# encoder.net
KiCad netlist of a schematic drawn in EAGLE
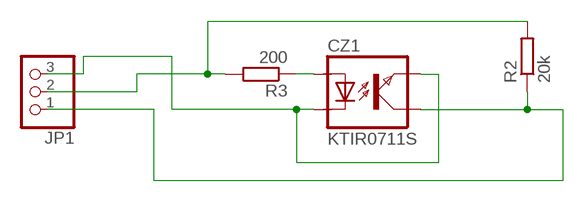
[diagram p0: schematic, sheet 1]

(export (version "E")
  (design (tool "Eeschema 10.0.6"))
  (components
    (comp (ref "CZ1")
      (value "KTIR0711S")
      (footprint "eagle-import:TOP")
      (libsource (lib "eagle-import") (part "KTIR0711S"))
    )
    (comp (ref "JP1")
      (value "PINHD-1X3")
      (footprint "eagle-import:1X03")
      (libsource (lib "eagle-import") (part "PINHD-1X3"))
    )
    (comp (ref "R2")
      (value "20k")
      (footprint "eagle-import:R0805")
      (libsource (lib "eagle-import") (part "R-EU_R0805"))
    )
    (comp (ref "R3")
      (value "200")
      (footprint "eagle-import:R0805")
      (libsource (lib "eagle-import") (part "R-EU_R0805"))
    )
  )
  (nets
    (net (code "1") (name "Net-(CZ1-PadANODA)") (class "Default")
      (node (ref "CZ1") (pin "ANODA") (pinfunction "ANODA_ANODA") (pintype "passive"))
      (node (ref "R3") (pin "1") (pinfunction "1_1") (pintype "passive"))
    )
    (net (code "2") (name "Net-(CZ1-PadEMITER)") (class "Default")
      (node (ref "CZ1") (pin "EMITER") (pinfunction "EMITER_EMITER") (pintype "bidirectional"))
      (node (ref "CZ1") (pin "KATODA") (pinfunction "KATODA_KATODA") (pintype "passive"))
      (node (ref "JP1") (pin "3") (pinfunction "3_3") (pintype "passive"))
    )
    (net (code "3") (name "Net-(CZ1-PadKOLEKTOR)") (class "Default")
      (node (ref "CZ1") (pin "KOLEKTOR") (pinfunction "KOLEKTOR_KOLEKTOR") (pintype "bidirectional"))
      (node (ref "JP1") (pin "1") (pinfunction "1_1") (pintype "passive"))
      (node (ref "R2") (pin "1") (pinfunction "1_1") (pintype "passive"))
    )
    (net (code "4") (name "Net-(JP1-Pad2)") (class "Default")
      (node (ref "JP1") (pin "2") (pinfunction "2_2") (pintype "passive"))
      (node (ref "R2") (pin "2") (pinfunction "2_2") (pintype "passive"))
      (node (ref "R3") (pin "2") (pinfunction "2_2") (pintype "passive"))
    )
  )
)
